# flow.net
KiCad netlist of a schematic drawn in Altium Designer
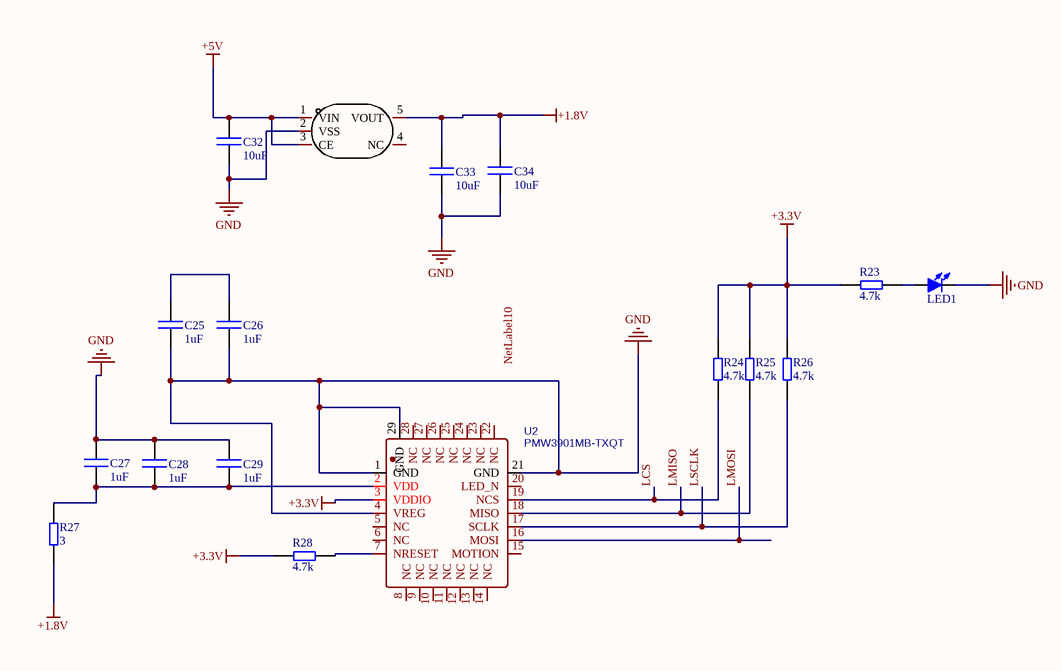
[diagram p0: flow.SchDoc]

(export (version "E")
  (design (tool "Eeschema 10.0.6"))
  (components
    (comp (ref "C25")
      (value "Cap")
      (footprint "Cap")
      (fields (field (name "ALTIUM_UNNAMED_1") "1uF"))
      (libsource (lib "self_schlib v1.8.6") (part "Cap"))
    )
    (comp (ref "C26")
      (value "Cap")
      (footprint "Cap")
      (fields (field (name "ALTIUM_UNNAMED_1") "1uF"))
      (libsource (lib "self_schlib v1.8.6") (part "Cap"))
    )
    (comp (ref "C27")
      (value "Cap")
      (footprint "Cap")
      (fields (field (name "ALTIUM_UNNAMED_1") "1uF"))
      (libsource (lib "self_schlib v1.8.6") (part "Cap"))
    )
    (comp (ref "C28")
      (value "Cap")
      (footprint "Cap")
      (fields (field (name "ALTIUM_UNNAMED_1") "1uF"))
      (libsource (lib "self_schlib v1.8.6") (part "Cap"))
    )
    (comp (ref "C29")
      (value "Cap")
      (footprint "Cap")
      (fields (field (name "ALTIUM_UNNAMED_1") "1uF"))
      (libsource (lib "self_schlib v1.8.6") (part "Cap"))
    )
    (comp (ref "C32")
      (value "Cap")
      (footprint "Cap")
      (fields (field (name "ALTIUM_UNNAMED_1") "10uF"))
      (libsource (lib "self_schlib v1.8.6") (part "Cap"))
    )
    (comp (ref "C33")
      (value "Cap")
      (footprint "Cap")
      (fields (field (name "ALTIUM_UNNAMED_1") "10uF"))
      (libsource (lib "self_schlib v1.8.6") (part "Cap"))
    )
    (comp (ref "C34")
      (value "Cap")
      (footprint "Cap")
      (fields (field (name "ALTIUM_UNNAMED_1") "10uF"))
      (libsource (lib "self_schlib v1.8.6") (part "Cap"))
    )
    (comp (ref "LED1")
      (value "LED")
      (footprint "LED-0603")
      (libsource (lib "self_schlib v1.8.6") (part "LED"))
    )
    (comp (ref "R23")
      (value "4.7K")
      (footprint "RES-0603")
      (fields (field (name "ALTIUM_UNNAMED_1") "4.7k"))
      (libsource (lib "self_schlib v1.8.6") (part "RES"))
    )
    (comp (ref "R24")
      (value "4.7K")
      (footprint "RES-0603")
      (fields (field (name "ALTIUM_UNNAMED_1") "4.7k"))
      (libsource (lib "self_schlib v1.8.6") (part "RES"))
    )
    (comp (ref "R25")
      (value "4.7K")
      (footprint "RES-0603")
      (fields (field (name "ALTIUM_UNNAMED_1") "4.7k"))
      (libsource (lib "self_schlib v1.8.6") (part "RES"))
    )
    (comp (ref "R26")
      (value "4.7K")
      (footprint "RES-0603")
      (fields (field (name "ALTIUM_UNNAMED_1") "4.7k"))
      (libsource (lib "self_schlib v1.8.6") (part "RES"))
    )
    (comp (ref "R27")
      (value "3")
      (footprint "RES-0603")
      (fields (field (name "ALTIUM_UNNAMED_1") "3"))
      (libsource (lib "self_schlib v1.8.6") (part "RES"))
    )
    (comp (ref "R28")
      (value "4.7K")
      (footprint "RES-0603")
      (fields (field (name "ALTIUM_UNNAMED_1") "4.7k"))
      (libsource (lib "self_schlib v1.8.6") (part "RES"))
    )
    (comp (ref "U2")
      (value "PMW3901MB-TXQT")
      (footprint "COB-28_L6.0-W6.0-P0.65-TL-EP")
      (fields (field (name "CONTRIBUTOR") "lcsc"))
      (libsource (lib "Sheet_1_2023-12-19") (part "PMW3901MB-TXQT"))
    )
    (comp (ref "U4")
      (value "ME6214C18M5G")
      (footprint "SOT-23-5_L3.0-W1.7-P0.95-LS2.8-BR")
      (fields (field (name "MANUFACTURER") "MICRONE(南京微盟)"))
      (libsource (lib "ME6214C18M5G1_ME6214C18M5G.schdoc") (part "ME6214C18M5G"))
    )
  )
  (nets
    (net (code "1") (name "+1.8V") (class "Default")
      (node (ref "C33") (pin "2") (pinfunction "2_2") (pintype "passive"))
      (node (ref "C34") (pin "2") (pinfunction "2_2") (pintype "passive"))
      (node (ref "R27") (pin "2") (pinfunction "2_2") (pintype "passive"))
      (node (ref "U4") (pin "5") (pinfunction "VOUT_5") (pintype "passive"))
    )
    (net (code "2") (name "+3.3V") (class "Default")
      (node (ref "R23") (pin "1") (pinfunction "1_1") (pintype "passive"))
      (node (ref "R24") (pin "2") (pinfunction "2_2") (pintype "passive"))
      (node (ref "R25") (pin "2") (pinfunction "2_2") (pintype "passive"))
      (node (ref "R26") (pin "2") (pinfunction "2_2") (pintype "passive"))
      (node (ref "R28") (pin "2") (pinfunction "2_2") (pintype "passive"))
      (node (ref "U2") (pin "3") (pinfunction "VDDIO_3") (pintype "passive"))
    )
    (net (code "3") (name "+5V") (class "Default")
      (node (ref "C32") (pin "2") (pinfunction "2_2") (pintype "passive"))
      (node (ref "U4") (pin "1") (pinfunction "VIN_1") (pintype "passive"))
      (node (ref "U4") (pin "3") (pinfunction "CE_3") (pintype "passive"))
    )
    (net (code "4") (name "/LCS") (class "Default")
      (node (ref "R24") (pin "1") (pinfunction "1_1") (pintype "passive"))
      (node (ref "U2") (pin "19") (pinfunction "NCS_19") (pintype "passive"))
    )
    (net (code "5") (name "/LMISO") (class "Default")
      (node (ref "R25") (pin "1") (pinfunction "1_1") (pintype "passive"))
      (node (ref "U2") (pin "18") (pinfunction "MISO_18") (pintype "passive"))
    )
    (net (code "6") (name "/LMOSI") (class "Default")
      (node (ref "U2") (pin "16") (pinfunction "MOSI_16") (pintype "passive"))
    )
    (net (code "7") (name "/LSCLK") (class "Default")
      (node (ref "R26") (pin "1") (pinfunction "1_1") (pintype "passive"))
      (node (ref "U2") (pin "17") (pinfunction "SCLK_17") (pintype "passive"))
    )
    (net (code "9") (name "GND") (class "Default")
      (node (ref "C25") (pin "1") (pinfunction "1_1") (pintype "passive"))
      (node (ref "C26") (pin "1") (pinfunction "1_1") (pintype "passive"))
      (node (ref "C27") (pin "2") (pinfunction "2_2") (pintype "passive"))
      (node (ref "C28") (pin "2") (pinfunction "2_2") (pintype "passive"))
      (node (ref "C29") (pin "2") (pinfunction "2_2") (pintype "passive"))
      (node (ref "C32") (pin "1") (pinfunction "1_1") (pintype "passive"))
      (node (ref "C33") (pin "1") (pinfunction "1_1") (pintype "passive"))
      (node (ref "C34") (pin "1") (pinfunction "1_1") (pintype "passive"))
      (node (ref "LED1") (pin "2") (pinfunction "2_2") (pintype "passive"))
      (node (ref "U2") (pin "1") (pinfunction "GND_1") (pintype "passive"))
      (node (ref "U2") (pin "21") (pinfunction "GND_21") (pintype "passive"))
      (node (ref "U2") (pin "29") (pinfunction "GND_29") (pintype "passive"))
      (node (ref "U2") (pin "4") (pinfunction "VREG_4") (pintype "passive"))
      (node (ref "U4") (pin "2") (pinfunction "VSS_2") (pintype "passive"))
    )
    (net (code "10") (name "Net-(C25-Pad2)") (class "Default")
      (node (ref "C25") (pin "2") (pinfunction "2_2") (pintype "passive"))
      (node (ref "C26") (pin "2") (pinfunction "2_2") (pintype "passive"))
    )
    (net (code "11") (name "Net-(LED1-Pad1)") (class "Default")
      (node (ref "LED1") (pin "1") (pinfunction "1_1") (pintype "passive"))
      (node (ref "R23") (pin "2") (pinfunction "2_2") (pintype "passive"))
    )
    (net (code "12") (name "Net-(U2-NRESET)") (class "Default")
      (node (ref "R28") (pin "1") (pinfunction "1_1") (pintype "passive"))
      (node (ref "U2") (pin "7") (pinfunction "NRESET_7") (pintype "passive"))
    )
    (net (code "13") (name "Net-(U2-VDD)") (class "Default")
      (node (ref "C27") (pin "1") (pinfunction "1_1") (pintype "passive"))
      (node (ref "C28") (pin "1") (pinfunction "1_1") (pintype "passive"))
      (node (ref "C29") (pin "1") (pinfunction "1_1") (pintype "passive"))
      (node (ref "R27") (pin "1") (pinfunction "1_1") (pintype "passive"))
      (node (ref "U2") (pin "2") (pinfunction "VDD_2") (pintype "passive"))
    )
    (net (code "14") (name "unconnected-(U2-LED_N-Pad20)") (class "Default")
      (node (ref "U2") (pin "20") (pinfunction "LED_N_20") (pintype "passive"))
    )
    (net (code "15") (name "unconnected-(U2-MOTION-Pad15)") (class "Default")
      (node (ref "U2") (pin "15") (pinfunction "MOTION_15") (pintype "passive"))
    )
    (net (code "16") (name "unconnected-(U2-NC-Pad5)") (class "Default")
      (node (ref "U2") (pin "5") (pinfunction "NC_5") (pintype "passive"))
    )
    (net (code "17") (name "unconnected-(U2-NC-Pad6)") (class "Default")
      (node (ref "U2") (pin "6") (pinfunction "NC_6") (pintype "passive"))
    )
    (net (code "18") (name "unconnected-(U2-NC-Pad8)") (class "Default")
      (node (ref "U2") (pin "8") (pinfunction "NC_8") (pintype "passive"))
    )
    (net (code "19") (name "unconnected-(U2-NC-Pad9)") (class "Default")
      (node (ref "U2") (pin "9") (pinfunction "NC_9") (pintype "passive"))
    )
    (net (code "20") (name "unconnected-(U2-NC-Pad10)") (class "Default")
      (node (ref "U2") (pin "10") (pinfunction "NC_10") (pintype "passive"))
    )
    (net (code "21") (name "unconnected-(U2-NC-Pad11)") (class "Default")
      (node (ref "U2") (pin "11") (pinfunction "NC_11") (pintype "passive"))
    )
    (net (code "22") (name "unconnected-(U2-NC-Pad12)") (class "Default")
      (node (ref "U2") (pin "12") (pinfunction "NC_12") (pintype "passive"))
    )
    (net (code "23") (name "unconnected-(U2-NC-Pad13)") (class "Default")
      (node (ref "U2") (pin "13") (pinfunction "NC_13") (pintype "passive"))
    )
    (net (code "24") (name "unconnected-(U2-NC-Pad14)") (class "Default")
      (node (ref "U2") (pin "14") (pinfunction "NC_14") (pintype "passive"))
    )
    (net (code "25") (name "unconnected-(U2-NC-Pad22)") (class "Default")
      (node (ref "U2") (pin "22") (pinfunction "NC_22") (pintype "passive"))
    )
    (net (code "26") (name "unconnected-(U2-NC-Pad23)") (class "Default")
      (node (ref "U2") (pin "23") (pinfunction "NC_23") (pintype "passive"))
    )
    (net (code "27") (name "unconnected-(U2-NC-Pad24)") (class "Default")
      (node (ref "U2") (pin "24") (pinfunction "NC_24") (pintype "passive"))
    )
    (net (code "28") (name "unconnected-(U2-NC-Pad25)") (class "Default")
      (node (ref "U2") (pin "25") (pinfunction "NC_25") (pintype "passive"))
    )
    (net (code "29") (name "unconnected-(U2-NC-Pad26)") (class "Default")
      (node (ref "U2") (pin "26") (pinfunction "NC_26") (pintype "passive"))
    )
    (net (code "30") (name "unconnected-(U2-NC-Pad27)") (class "Default")
      (node (ref "U2") (pin "27") (pinfunction "NC_27") (pintype "passive"))
    )
    (net (code "31") (name "unconnected-(U2-NC-Pad28)") (class "Default")
      (node (ref "U2") (pin "28") (pinfunction "NC_28") (pintype "passive"))
    )
    (net (code "32") (name "unconnected-(U4-NC-Pad4)") (class "Default")
      (node (ref "U4") (pin "4") (pinfunction "NC_4") (pintype "passive"))
    )
  )
)
